# CAN.net
KiCad netlist of a schematic drawn in Altium Designer
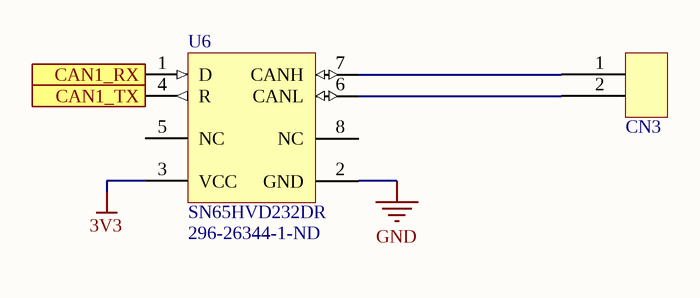
[diagram p0: CAN.SchDoc]

(export (version "E")
  (design (tool "Eeschema 10.0.6"))
  (components
    (comp (ref "CN3")
      (value "640456-2")
      (footprint "640456-2")
      (description "CONN HEADER VERT 2POS .100 TIN")
      (fields (field (name "MADE BY") "Robert Keen"))
      (libsource (lib "AUVic_Integrated_Library_Connectors") (part "2x1 Male Header, Friction Lock"))
    )
    (comp (ref "U6")
      (value "SN65HVD232DR")
      (footprint "8-SOIC")
      (description "IC CAN TRANSCEIVER 3.3V 8-SOIC")
      (fields (field (name "SUPPLIER PART NUMBER 1") "296-26344-1-ND") (field (name "MADE BY") "Robert Keen"))
      (libsource (lib "AUVic_Integrated_Library_Interface") (part "CAN Half Duplex SN65HVD232DR"))
    )
  )
  (nets
    (net (code "1") (name "/CAN1_RX") (class "Default")
      (node (ref "U6") (pin "1") (pinfunction "D_1") (pintype "input"))
    )
    (net (code "2") (name "/CAN1_TX") (class "Default")
      (node (ref "U6") (pin "4") (pinfunction "R_4") (pintype "output"))
    )
    (net (code "3") (name "3V3") (class "Default")
      (node (ref "U6") (pin "3") (pinfunction "VCC_3") (pintype "power_in"))
    )
    (net (code "4") (name "GND") (class "Default")
      (node (ref "U6") (pin "2") (pinfunction "GND_2") (pintype "power_in"))
    )
    (net (code "5") (name "Net-(U6-CANH)") (class "Default")
      (node (ref "CN3") (pin "1") (pintype "passive"))
      (node (ref "U6") (pin "7") (pinfunction "CANH_7") (pintype "bidirectional"))
    )
    (net (code "6") (name "Net-(U6-CANL)") (class "Default")
      (node (ref "CN3") (pin "2") (pintype "passive"))
      (node (ref "U6") (pin "6") (pinfunction "CANL_6") (pintype "bidirectional"))
    )
    (net (code "7") (name "unconnected-(U6-NC-Pad5)") (class "Default")
      (node (ref "U6") (pin "5") (pinfunction "NC_5") (pintype "passive"))
    )
    (net (code "8") (name "unconnected-(U6-NC-Pad8)") (class "Default")
      (node (ref "U6") (pin "8") (pinfunction "NC_8") (pintype "passive"))
    )
  )
)
